# Boost.net
KiCad netlist of a schematic drawn in EAGLE
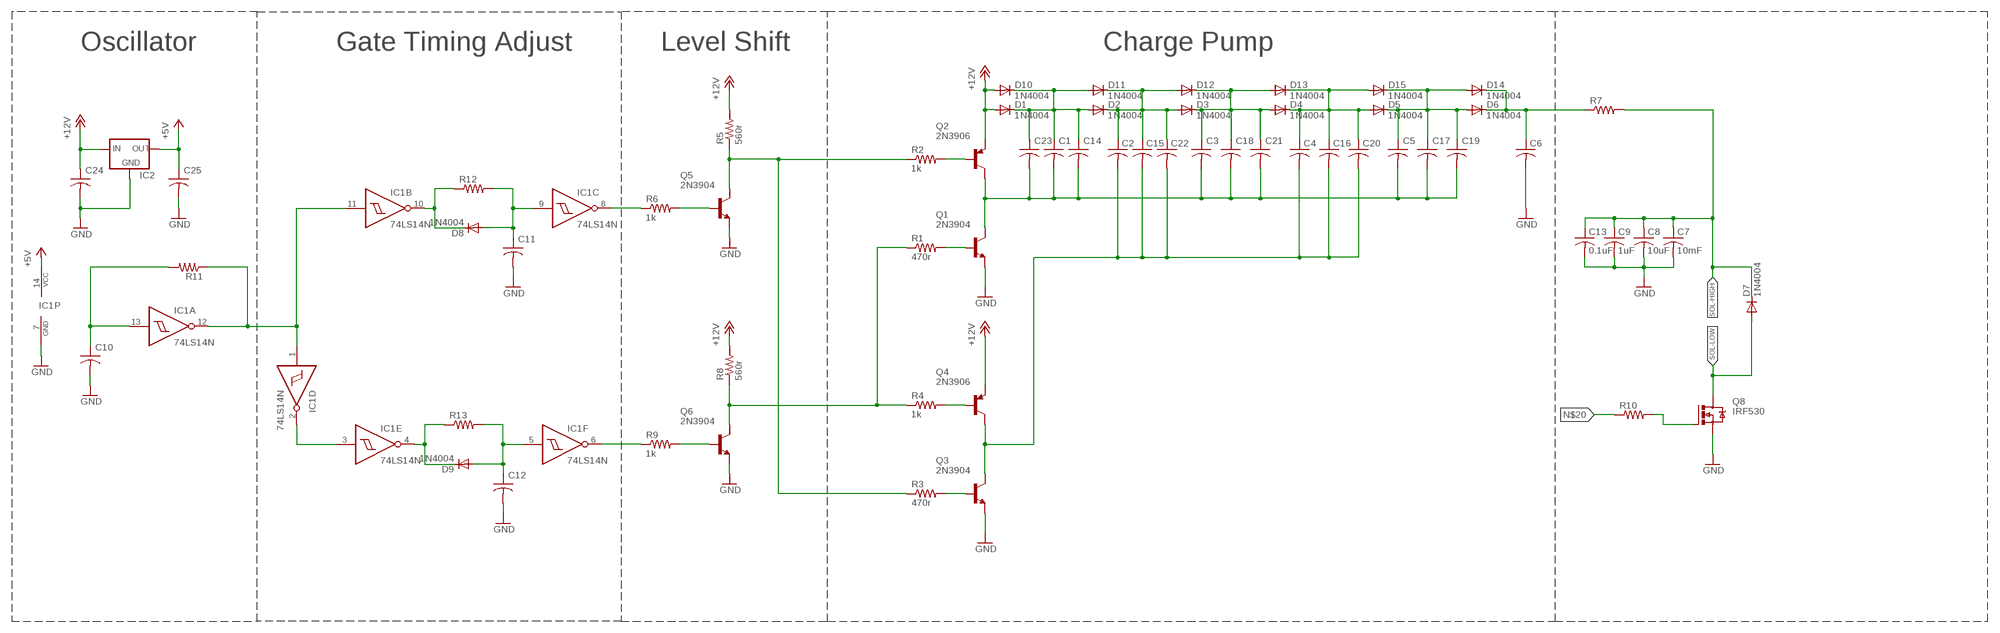
[diagram p0: schematic, sheet 1]

(export (version "E")
  (design (tool "Eeschema 10.0.6"))
  (components
    (comp (ref "C1")
      (value "C-US050-024X044")
      (footprint "eagle-import:C050-024X044")
      (libsource (lib "eagle-import") (part "C-US050-024X044"))
    )
    (comp (ref "C2")
      (value "C-US050-024X044")
      (footprint "eagle-import:C050-024X044")
      (libsource (lib "eagle-import") (part "C-US050-024X044"))
    )
    (comp (ref "C3")
      (value "C-US050-024X044")
      (footprint "eagle-import:C050-024X044")
      (libsource (lib "eagle-import") (part "C-US050-024X044"))
    )
    (comp (ref "C4")
      (value "C-US050-024X044")
      (footprint "eagle-import:C050-024X044")
      (libsource (lib "eagle-import") (part "C-US050-024X044"))
    )
    (comp (ref "C5")
      (value "C-US050-024X044")
      (footprint "eagle-import:C050-024X044")
      (libsource (lib "eagle-import") (part "C-US050-024X044"))
    )
    (comp (ref "C6")
      (value "C-US050-024X044")
      (footprint "eagle-import:C050-024X044")
      (libsource (lib "eagle-import") (part "C-US050-024X044"))
    )
    (comp (ref "C7")
      (value "10mF")
      (footprint "eagle-import:C050-024X044")
      (libsource (lib "eagle-import") (part "C-US050-024X044"))
    )
    (comp (ref "C8")
      (value "10uF")
      (footprint "eagle-import:C050-024X044")
      (libsource (lib "eagle-import") (part "C-US050-024X044"))
    )
    (comp (ref "C9")
      (value "1uF")
      (footprint "eagle-import:C050-024X044")
      (libsource (lib "eagle-import") (part "C-US050-024X044"))
    )
    (comp (ref "C10")
      (value "C-US050-024X044")
      (footprint "eagle-import:C050-024X044")
      (libsource (lib "eagle-import") (part "C-US050-024X044"))
    )
    (comp (ref "C11")
      (value "C-US050-024X044")
      (footprint "eagle-import:C050-024X044")
      (libsource (lib "eagle-import") (part "C-US050-024X044"))
    )
    (comp (ref "C12")
      (value "C-US050-024X044")
      (footprint "eagle-import:C050-024X044")
      (libsource (lib "eagle-import") (part "C-US050-024X044"))
    )
    (comp (ref "C13")
      (value "0.1uF")
      (footprint "eagle-import:C050-024X044")
      (libsource (lib "eagle-import") (part "C-US050-024X044"))
    )
    (comp (ref "C14")
      (value "C-US050-024X044")
      (footprint "eagle-import:C050-024X044")
      (libsource (lib "eagle-import") (part "C-US050-024X044"))
    )
    (comp (ref "C15")
      (value "C-US050-024X044")
      (footprint "eagle-import:C050-024X044")
      (libsource (lib "eagle-import") (part "C-US050-024X044"))
    )
    (comp (ref "C16")
      (value "C-US050-024X044")
      (footprint "eagle-import:C050-024X044")
      (libsource (lib "eagle-import") (part "C-US050-024X044"))
    )
    (comp (ref "C17")
      (value "C-US050-024X044")
      (footprint "eagle-import:C050-024X044")
      (libsource (lib "eagle-import") (part "C-US050-024X044"))
    )
    (comp (ref "C18")
      (value "C-US050-024X044")
      (footprint "eagle-import:C050-024X044")
      (libsource (lib "eagle-import") (part "C-US050-024X044"))
    )
    (comp (ref "C19")
      (value "C-US050-024X044")
      (footprint "eagle-import:C050-024X044")
      (libsource (lib "eagle-import") (part "C-US050-024X044"))
    )
    (comp (ref "C20")
      (value "C-US050-024X044")
      (footprint "eagle-import:C050-024X044")
      (libsource (lib "eagle-import") (part "C-US050-024X044"))
    )
    (comp (ref "C21")
      (value "C-US050-024X044")
      (footprint "eagle-import:C050-024X044")
      (libsource (lib "eagle-import") (part "C-US050-024X044"))
    )
    (comp (ref "C22")
      (value "C-US050-024X044")
      (footprint "eagle-import:C050-024X044")
      (libsource (lib "eagle-import") (part "C-US050-024X044"))
    )
    (comp (ref "C23")
      (value "C-US050-024X044")
      (footprint "eagle-import:C050-024X044")
      (libsource (lib "eagle-import") (part "C-US050-024X044"))
    )
    (comp (ref "C24")
      (value "C-US050-024X044")
      (footprint "eagle-import:C050-024X044")
      (libsource (lib "eagle-import") (part "C-US050-024X044"))
    )
    (comp (ref "C25")
      (value "C-US050-024X044")
      (footprint "eagle-import:C050-024X044")
      (libsource (lib "eagle-import") (part "C-US050-024X044"))
    )
    (comp (ref "D1")
      (value "1N4004")
      (footprint "eagle-import:DO41-10")
      (libsource (lib "eagle-import") (part "1N4004"))
    )
    (comp (ref "D2")
      (value "1N4004")
      (footprint "eagle-import:DO41-10")
      (libsource (lib "eagle-import") (part "1N4004"))
    )
    (comp (ref "D3")
      (value "1N4004")
      (footprint "eagle-import:DO41-10")
      (libsource (lib "eagle-import") (part "1N4004"))
    )
    (comp (ref "D4")
      (value "1N4004")
      (footprint "eagle-import:DO41-10")
      (libsource (lib "eagle-import") (part "1N4004"))
    )
    (comp (ref "D5")
      (value "1N4004")
      (footprint "eagle-import:DO41-10")
      (libsource (lib "eagle-import") (part "1N4004"))
    )
    (comp (ref "D6")
      (value "1N4004")
      (footprint "eagle-import:DO41-10")
      (libsource (lib "eagle-import") (part "1N4004"))
    )
    (comp (ref "D7")
      (value "1N4004")
      (footprint "eagle-import:DO41-10")
      (libsource (lib "eagle-import") (part "1N4004"))
    )
    (comp (ref "D8")
      (value "1N4004")
      (footprint "eagle-import:DO41-10")
      (libsource (lib "eagle-import") (part "1N4004"))
    )
    (comp (ref "D9")
      (value "1N4004")
      (footprint "eagle-import:DO41-10")
      (libsource (lib "eagle-import") (part "1N4004"))
    )
    (comp (ref "D10")
      (value "1N4004")
      (footprint "eagle-import:DO41-10")
      (libsource (lib "eagle-import") (part "1N4004"))
    )
    (comp (ref "D11")
      (value "1N4004")
      (footprint "eagle-import:DO41-10")
      (libsource (lib "eagle-import") (part "1N4004"))
    )
    (comp (ref "D12")
      (value "1N4004")
      (footprint "eagle-import:DO41-10")
      (libsource (lib "eagle-import") (part "1N4004"))
    )
    (comp (ref "D13")
      (value "1N4004")
      (footprint "eagle-import:DO41-10")
      (libsource (lib "eagle-import") (part "1N4004"))
    )
    (comp (ref "D14")
      (value "1N4004")
      (footprint "eagle-import:DO41-10")
      (libsource (lib "eagle-import") (part "1N4004"))
    )
    (comp (ref "D15")
      (value "1N4004")
      (footprint "eagle-import:DO41-10")
      (libsource (lib "eagle-import") (part "1N4004"))
    )
    (comp (ref "IC1")
      (value "74LS14N")
      (footprint "eagle-import:DIL14")
      (libsource (lib "eagle-import") (part "7414NLS"))
    )
    (comp (ref "IC2")
      (value "78XXS")
      (footprint "eagle-import:78XXS")
      (libsource (lib "eagle-import") (part "78XXS"))
    )
    (comp (ref "Q1")
      (value "2N3904")
      (footprint "eagle-import:TO92")
      (libsource (lib "eagle-import") (part "2N3904"))
    )
    (comp (ref "Q2")
      (value "2N3906")
      (footprint "eagle-import:TO92")
      (libsource (lib "eagle-import") (part "2N3906"))
    )
    (comp (ref "Q3")
      (value "2N3904")
      (footprint "eagle-import:TO92")
      (libsource (lib "eagle-import") (part "2N3904"))
    )
    (comp (ref "Q4")
      (value "2N3906")
      (footprint "eagle-import:TO92")
      (libsource (lib "eagle-import") (part "2N3906"))
    )
    (comp (ref "Q5")
      (value "2N3904")
      (footprint "eagle-import:TO92")
      (libsource (lib "eagle-import") (part "2N3904"))
    )
    (comp (ref "Q6")
      (value "2N3904")
      (footprint "eagle-import:TO92")
      (libsource (lib "eagle-import") (part "2N3904"))
    )
    (comp (ref "Q8")
      (value "IRF530")
      (footprint "eagle-import:TO220BV")
      (libsource (lib "eagle-import") (part "IRF530"))
    )
    (comp (ref "R1")
      (value "470r")
      (footprint "eagle-import:0207_10")
      (libsource (lib "eagle-import") (part "R-US_0207/10"))
    )
    (comp (ref "R2")
      (value "1k")
      (footprint "eagle-import:0207_10")
      (libsource (lib "eagle-import") (part "R-US_0207/10"))
    )
    (comp (ref "R3")
      (value "470r")
      (footprint "eagle-import:0207_10")
      (libsource (lib "eagle-import") (part "R-US_0207/10"))
    )
    (comp (ref "R4")
      (value "1k")
      (footprint "eagle-import:0207_10")
      (libsource (lib "eagle-import") (part "R-US_0207/10"))
    )
    (comp (ref "R5")
      (value "560r")
      (footprint "eagle-import:0207_10")
      (libsource (lib "eagle-import") (part "R-US_0207/10"))
    )
    (comp (ref "R6")
      (value "1k")
      (footprint "eagle-import:0207_10")
      (libsource (lib "eagle-import") (part "R-US_0207/10"))
    )
    (comp (ref "R7")
      (value "R-US_0207/10")
      (footprint "eagle-import:0207_10")
      (libsource (lib "eagle-import") (part "R-US_0207/10"))
    )
    (comp (ref "R8")
      (value "560r")
      (footprint "eagle-import:0207_10")
      (libsource (lib "eagle-import") (part "R-US_0207/10"))
    )
    (comp (ref "R9")
      (value "1k")
      (footprint "eagle-import:0207_10")
      (libsource (lib "eagle-import") (part "R-US_0207/10"))
    )
    (comp (ref "R10")
      (value "R-US_0207/10")
      (footprint "eagle-import:0207_10")
      (libsource (lib "eagle-import") (part "R-US_0207/10"))
    )
    (comp (ref "R11")
      (value "R-US_0207/10")
      (footprint "eagle-import:0207_10")
      (libsource (lib "eagle-import") (part "R-US_0207/10"))
    )
    (comp (ref "R12")
      (value "R-US_0207/10")
      (footprint "eagle-import:0207_10")
      (libsource (lib "eagle-import") (part "R-US_0207/10"))
    )
    (comp (ref "R13")
      (value "R-US_0207/10")
      (footprint "eagle-import:0207_10")
      (libsource (lib "eagle-import") (part "R-US_0207/10"))
    )
  )
  (nets
    (net (code "1") (name "+5V") (class "Default")
      (node (ref "C25") (pin "1") (pinfunction "1_1") (pintype "passive"))
      (node (ref "IC1") (pin "14") (pinfunction "VCC_14") (pintype "power_in"))
      (node (ref "IC2") (pin "OUT") (pinfunction "OUT_OUT") (pintype "passive"))
    )
    (net (code "2") (name "+12V") (class "Default")
      (node (ref "C24") (pin "1") (pinfunction "1_1") (pintype "passive"))
      (node (ref "D1") (pin "A") (pinfunction "A_A") (pintype "passive"))
      (node (ref "D10") (pin "A") (pinfunction "A_A") (pintype "passive"))
      (node (ref "IC2") (pin "IN") (pinfunction "IN_IN") (pintype "input"))
      (node (ref "Q2") (pin "3") (pinfunction "E_3") (pintype "passive"))
      (node (ref "Q4") (pin "3") (pinfunction "E_3") (pintype "passive"))
      (node (ref "R5") (pin "2") (pinfunction "2_2") (pintype "passive"))
      (node (ref "R8") (pin "2") (pinfunction "2_2") (pintype "passive"))
    )
    (net (code "3") (name "GND") (class "Default")
      (node (ref "C10") (pin "2") (pinfunction "2_2") (pintype "passive"))
      (node (ref "C11") (pin "2") (pinfunction "2_2") (pintype "passive"))
      (node (ref "C12") (pin "2") (pinfunction "2_2") (pintype "passive"))
      (node (ref "C13") (pin "2") (pinfunction "2_2") (pintype "passive"))
      (node (ref "C24") (pin "2") (pinfunction "2_2") (pintype "passive"))
      (node (ref "C25") (pin "2") (pinfunction "2_2") (pintype "passive"))
      (node (ref "C6") (pin "2") (pinfunction "2_2") (pintype "passive"))
      (node (ref "C7") (pin "2") (pinfunction "2_2") (pintype "passive"))
      (node (ref "C8") (pin "2") (pinfunction "2_2") (pintype "passive"))
      (node (ref "C9") (pin "2") (pinfunction "2_2") (pintype "passive"))
      (node (ref "IC1") (pin "7") (pinfunction "GND_7") (pintype "power_in"))
      (node (ref "IC2") (pin "GND") (pinfunction "GND_GND") (pintype "input"))
      (node (ref "Q1") (pin "3") (pinfunction "E_3") (pintype "passive"))
      (node (ref "Q3") (pin "3") (pinfunction "E_3") (pintype "passive"))
      (node (ref "Q5") (pin "3") (pinfunction "E_3") (pintype "passive"))
      (node (ref "Q6") (pin "3") (pinfunction "E_3") (pintype "passive"))
      (node (ref "Q8") (pin "S") (pinfunction "S_S") (pintype "passive"))
    )
    (net (code "4") (name "N$20") (class "Default")
      (node (ref "R10") (pin "1") (pinfunction "1_1") (pintype "passive"))
    )
    (net (code "5") (name "Net-(C1-Pad1)") (class "Default")
      (node (ref "C1") (pin "1") (pinfunction "1_1") (pintype "passive"))
      (node (ref "C14") (pin "1") (pinfunction "1_1") (pintype "passive"))
      (node (ref "C23") (pin "1") (pinfunction "1_1") (pintype "passive"))
      (node (ref "D1") (pin "C") (pinfunction "C_C") (pintype "passive"))
      (node (ref "D10") (pin "C") (pinfunction "C_C") (pintype "passive"))
      (node (ref "D11") (pin "A") (pinfunction "A_A") (pintype "passive"))
      (node (ref "D2") (pin "A") (pinfunction "A_A") (pintype "passive"))
    )
    (net (code "6") (name "Net-(C6-Pad1)") (class "Default")
      (node (ref "C6") (pin "1") (pinfunction "1_1") (pintype "passive"))
      (node (ref "D14") (pin "C") (pinfunction "C_C") (pintype "passive"))
      (node (ref "D6") (pin "C") (pinfunction "C_C") (pintype "passive"))
      (node (ref "R7") (pin "1") (pinfunction "1_1") (pintype "passive"))
    )
    (net (code "7") (name "Net-(C15-Pad1)") (class "Default")
      (node (ref "C15") (pin "1") (pinfunction "1_1") (pintype "passive"))
      (node (ref "C2") (pin "1") (pinfunction "1_1") (pintype "passive"))
      (node (ref "C22") (pin "1") (pinfunction "1_1") (pintype "passive"))
      (node (ref "D11") (pin "C") (pinfunction "C_C") (pintype "passive"))
      (node (ref "D12") (pin "A") (pinfunction "A_A") (pintype "passive"))
      (node (ref "D2") (pin "C") (pinfunction "C_C") (pintype "passive"))
      (node (ref "D3") (pin "A") (pinfunction "A_A") (pintype "passive"))
    )
    (net (code "8") (name "Net-(C16-Pad1)") (class "Default")
      (node (ref "C16") (pin "1") (pinfunction "1_1") (pintype "passive"))
      (node (ref "C20") (pin "1") (pinfunction "1_1") (pintype "passive"))
      (node (ref "C4") (pin "1") (pinfunction "1_1") (pintype "passive"))
      (node (ref "D13") (pin "C") (pinfunction "C_C") (pintype "passive"))
      (node (ref "D15") (pin "A") (pinfunction "A_A") (pintype "passive"))
      (node (ref "D4") (pin "C") (pinfunction "C_C") (pintype "passive"))
      (node (ref "D5") (pin "A") (pinfunction "A_A") (pintype "passive"))
    )
    (net (code "9") (name "Net-(C17-Pad1)") (class "Default")
      (node (ref "C17") (pin "1") (pinfunction "1_1") (pintype "passive"))
      (node (ref "C19") (pin "1") (pinfunction "1_1") (pintype "passive"))
      (node (ref "C5") (pin "1") (pinfunction "1_1") (pintype "passive"))
      (node (ref "D14") (pin "A") (pinfunction "A_A") (pintype "passive"))
      (node (ref "D15") (pin "C") (pinfunction "C_C") (pintype "passive"))
      (node (ref "D5") (pin "C") (pinfunction "C_C") (pintype "passive"))
      (node (ref "D6") (pin "A") (pinfunction "A_A") (pintype "passive"))
    )
    (net (code "10") (name "Net-(C18-Pad1)") (class "Default")
      (node (ref "C18") (pin "1") (pinfunction "1_1") (pintype "passive"))
      (node (ref "C21") (pin "1") (pinfunction "1_1") (pintype "passive"))
      (node (ref "C3") (pin "1") (pinfunction "1_1") (pintype "passive"))
      (node (ref "D12") (pin "C") (pinfunction "C_C") (pintype "passive"))
      (node (ref "D13") (pin "A") (pinfunction "A_A") (pintype "passive"))
      (node (ref "D3") (pin "C") (pinfunction "C_C") (pintype "passive"))
      (node (ref "D4") (pin "A") (pinfunction "A_A") (pintype "passive"))
    )
    (net (code "11") (name "Net-(IC1A-I)") (class "Default")
      (node (ref "C10") (pin "1") (pinfunction "1_1") (pintype "passive"))
      (node (ref "IC1") (pin "13") (pinfunction "I_13") (pintype "input"))
      (node (ref "R11") (pin "2") (pinfunction "2_2") (pintype "passive"))
    )
    (net (code "12") (name "Net-(IC1A-O)") (class "Default")
      (node (ref "IC1") (pin "1") (pinfunction "I_1") (pintype "input"))
      (node (ref "IC1") (pin "11") (pinfunction "I_11") (pintype "input"))
      (node (ref "IC1") (pin "12") (pinfunction "O_12") (pintype "output"))
      (node (ref "R11") (pin "1") (pinfunction "1_1") (pintype "passive"))
    )
    (net (code "13") (name "Net-(IC1B-O)") (class "Default")
      (node (ref "D8") (pin "C") (pinfunction "C_C") (pintype "passive"))
      (node (ref "IC1") (pin "10") (pinfunction "O_10") (pintype "output"))
      (node (ref "R12") (pin "1") (pinfunction "1_1") (pintype "passive"))
    )
    (net (code "14") (name "Net-(IC1C-I)") (class "Default")
      (node (ref "C11") (pin "1") (pinfunction "1_1") (pintype "passive"))
      (node (ref "D8") (pin "A") (pinfunction "A_A") (pintype "passive"))
      (node (ref "IC1") (pin "9") (pinfunction "I_9") (pintype "input"))
      (node (ref "R12") (pin "2") (pinfunction "2_2") (pintype "passive"))
    )
    (net (code "15") (name "Net-(IC1C-O)") (class "Default")
      (node (ref "IC1") (pin "8") (pinfunction "O_8") (pintype "output"))
      (node (ref "R6") (pin "1") (pinfunction "1_1") (pintype "passive"))
    )
    (net (code "16") (name "Net-(IC1D-O)") (class "Default")
      (node (ref "IC1") (pin "2") (pinfunction "O_2") (pintype "output"))
      (node (ref "IC1") (pin "3") (pinfunction "I_3") (pintype "input"))
    )
    (net (code "17") (name "Net-(IC1E-O)") (class "Default")
      (node (ref "D9") (pin "C") (pinfunction "C_C") (pintype "passive"))
      (node (ref "IC1") (pin "4") (pinfunction "O_4") (pintype "output"))
      (node (ref "R13") (pin "1") (pinfunction "1_1") (pintype "passive"))
    )
    (net (code "18") (name "Net-(IC1F-I)") (class "Default")
      (node (ref "C12") (pin "1") (pinfunction "1_1") (pintype "passive"))
      (node (ref "D9") (pin "A") (pinfunction "A_A") (pintype "passive"))
      (node (ref "IC1") (pin "5") (pinfunction "I_5") (pintype "input"))
      (node (ref "R13") (pin "2") (pinfunction "2_2") (pintype "passive"))
    )
    (net (code "19") (name "Net-(IC1F-O)") (class "Default")
      (node (ref "IC1") (pin "6") (pinfunction "O_6") (pintype "output"))
      (node (ref "R9") (pin "1") (pinfunction "1_1") (pintype "passive"))
    )
    (net (code "20") (name "Net-(Q1-B)") (class "Default")
      (node (ref "Q1") (pin "2") (pinfunction "B_2") (pintype "passive"))
      (node (ref "R1") (pin "2") (pinfunction "2_2") (pintype "passive"))
    )
    (net (code "21") (name "Net-(Q1-C)") (class "Default")
      (node (ref "C1") (pin "2") (pinfunction "2_2") (pintype "passive"))
      (node (ref "C14") (pin "2") (pinfunction "2_2") (pintype "passive"))
      (node (ref "C17") (pin "2") (pinfunction "2_2") (pintype "passive"))
      (node (ref "C18") (pin "2") (pinfunction "2_2") (pintype "passive"))
      (node (ref "C19") (pin "2") (pinfunction "2_2") (pintype "passive"))
      (node (ref "C21") (pin "2") (pinfunction "2_2") (pintype "passive"))
      (node (ref "C23") (pin "2") (pinfunction "2_2") (pintype "passive"))
      (node (ref "C3") (pin "2") (pinfunction "2_2") (pintype "passive"))
      (node (ref "C5") (pin "2") (pinfunction "2_2") (pintype "passive"))
      (node (ref "Q1") (pin "1") (pinfunction "C_1") (pintype "passive"))
      (node (ref "Q2") (pin "1") (pinfunction "C_1") (pintype "passive"))
    )
    (net (code "22") (name "Net-(Q2-B)") (class "Default")
      (node (ref "Q2") (pin "2") (pinfunction "B_2") (pintype "passive"))
      (node (ref "R2") (pin "2") (pinfunction "2_2") (pintype "passive"))
    )
    (net (code "23") (name "Net-(Q3-B)") (class "Default")
      (node (ref "Q3") (pin "2") (pinfunction "B_2") (pintype "passive"))
      (node (ref "R3") (pin "2") (pinfunction "2_2") (pintype "passive"))
    )
    (net (code "24") (name "Net-(Q3-C)") (class "Default")
      (node (ref "C15") (pin "2") (pinfunction "2_2") (pintype "passive"))
      (node (ref "C16") (pin "2") (pinfunction "2_2") (pintype "passive"))
      (node (ref "C2") (pin "2") (pinfunction "2_2") (pintype "passive"))
      (node (ref "C20") (pin "2") (pinfunction "2_2") (pintype "passive"))
      (node (ref "C22") (pin "2") (pinfunction "2_2") (pintype "passive"))
      (node (ref "C4") (pin "2") (pinfunction "2_2") (pintype "passive"))
      (node (ref "Q3") (pin "1") (pinfunction "C_1") (pintype "passive"))
      (node (ref "Q4") (pin "1") (pinfunction "C_1") (pintype "passive"))
    )
    (net (code "25") (name "Net-(Q4-B)") (class "Default")
      (node (ref "Q4") (pin "2") (pinfunction "B_2") (pintype "passive"))
      (node (ref "R4") (pin "2") (pinfunction "2_2") (pintype "passive"))
    )
    (net (code "26") (name "Net-(Q5-B)") (class "Default")
      (node (ref "Q5") (pin "2") (pinfunction "B_2") (pintype "passive"))
      (node (ref "R6") (pin "2") (pinfunction "2_2") (pintype "passive"))
    )
    (net (code "27") (name "Net-(Q5-C)") (class "Default")
      (node (ref "Q5") (pin "1") (pinfunction "C_1") (pintype "passive"))
      (node (ref "R2") (pin "1") (pinfunction "1_1") (pintype "passive"))
      (node (ref "R3") (pin "1") (pinfunction "1_1") (pintype "passive"))
      (node (ref "R5") (pin "1") (pinfunction "1_1") (pintype "passive"))
    )
    (net (code "28") (name "Net-(Q6-B)") (class "Default")
      (node (ref "Q6") (pin "2") (pinfunction "B_2") (pintype "passive"))
      (node (ref "R9") (pin "2") (pinfunction "2_2") (pintype "passive"))
    )
    (net (code "29") (name "Net-(Q6-C)") (class "Default")
      (node (ref "Q6") (pin "1") (pinfunction "C_1") (pintype "passive"))
      (node (ref "R1") (pin "1") (pinfunction "1_1") (pintype "passive"))
      (node (ref "R4") (pin "1") (pinfunction "1_1") (pintype "passive"))
      (node (ref "R8") (pin "1") (pinfunction "1_1") (pintype "passive"))
    )
    (net (code "30") (name "Net-(Q8-PadG)") (class "Default")
      (node (ref "Q8") (pin "G") (pinfunction "G_G") (pintype "passive"))
      (node (ref "R10") (pin "2") (pinfunction "2_2") (pintype "passive"))
    )
    (net (code "31") (name "SOL-HIGH") (class "Default")
      (node (ref "C13") (pin "1") (pinfunction "1_1") (pintype "passive"))
      (node (ref "C7") (pin "1") (pinfunction "1_1") (pintype "passive"))
      (node (ref "C8") (pin "1") (pinfunction "1_1") (pintype "passive"))
      (node (ref "C9") (pin "1") (pinfunction "1_1") (pintype "passive"))
      (node (ref "D7") (pin "C") (pinfunction "C_C") (pintype "passive"))
      (node (ref "R7") (pin "2") (pinfunction "2_2") (pintype "passive"))
    )
    (net (code "32") (name "SOL-LOW") (class "Default")
      (node (ref "D7") (pin "A") (pinfunction "A_A") (pintype "passive"))
      (node (ref "Q8") (pin "D") (pinfunction "D_D") (pintype "passive"))
    )
  )
)
